# TOP_LED.net
KiCad netlist of a schematic drawn in Altium Designer
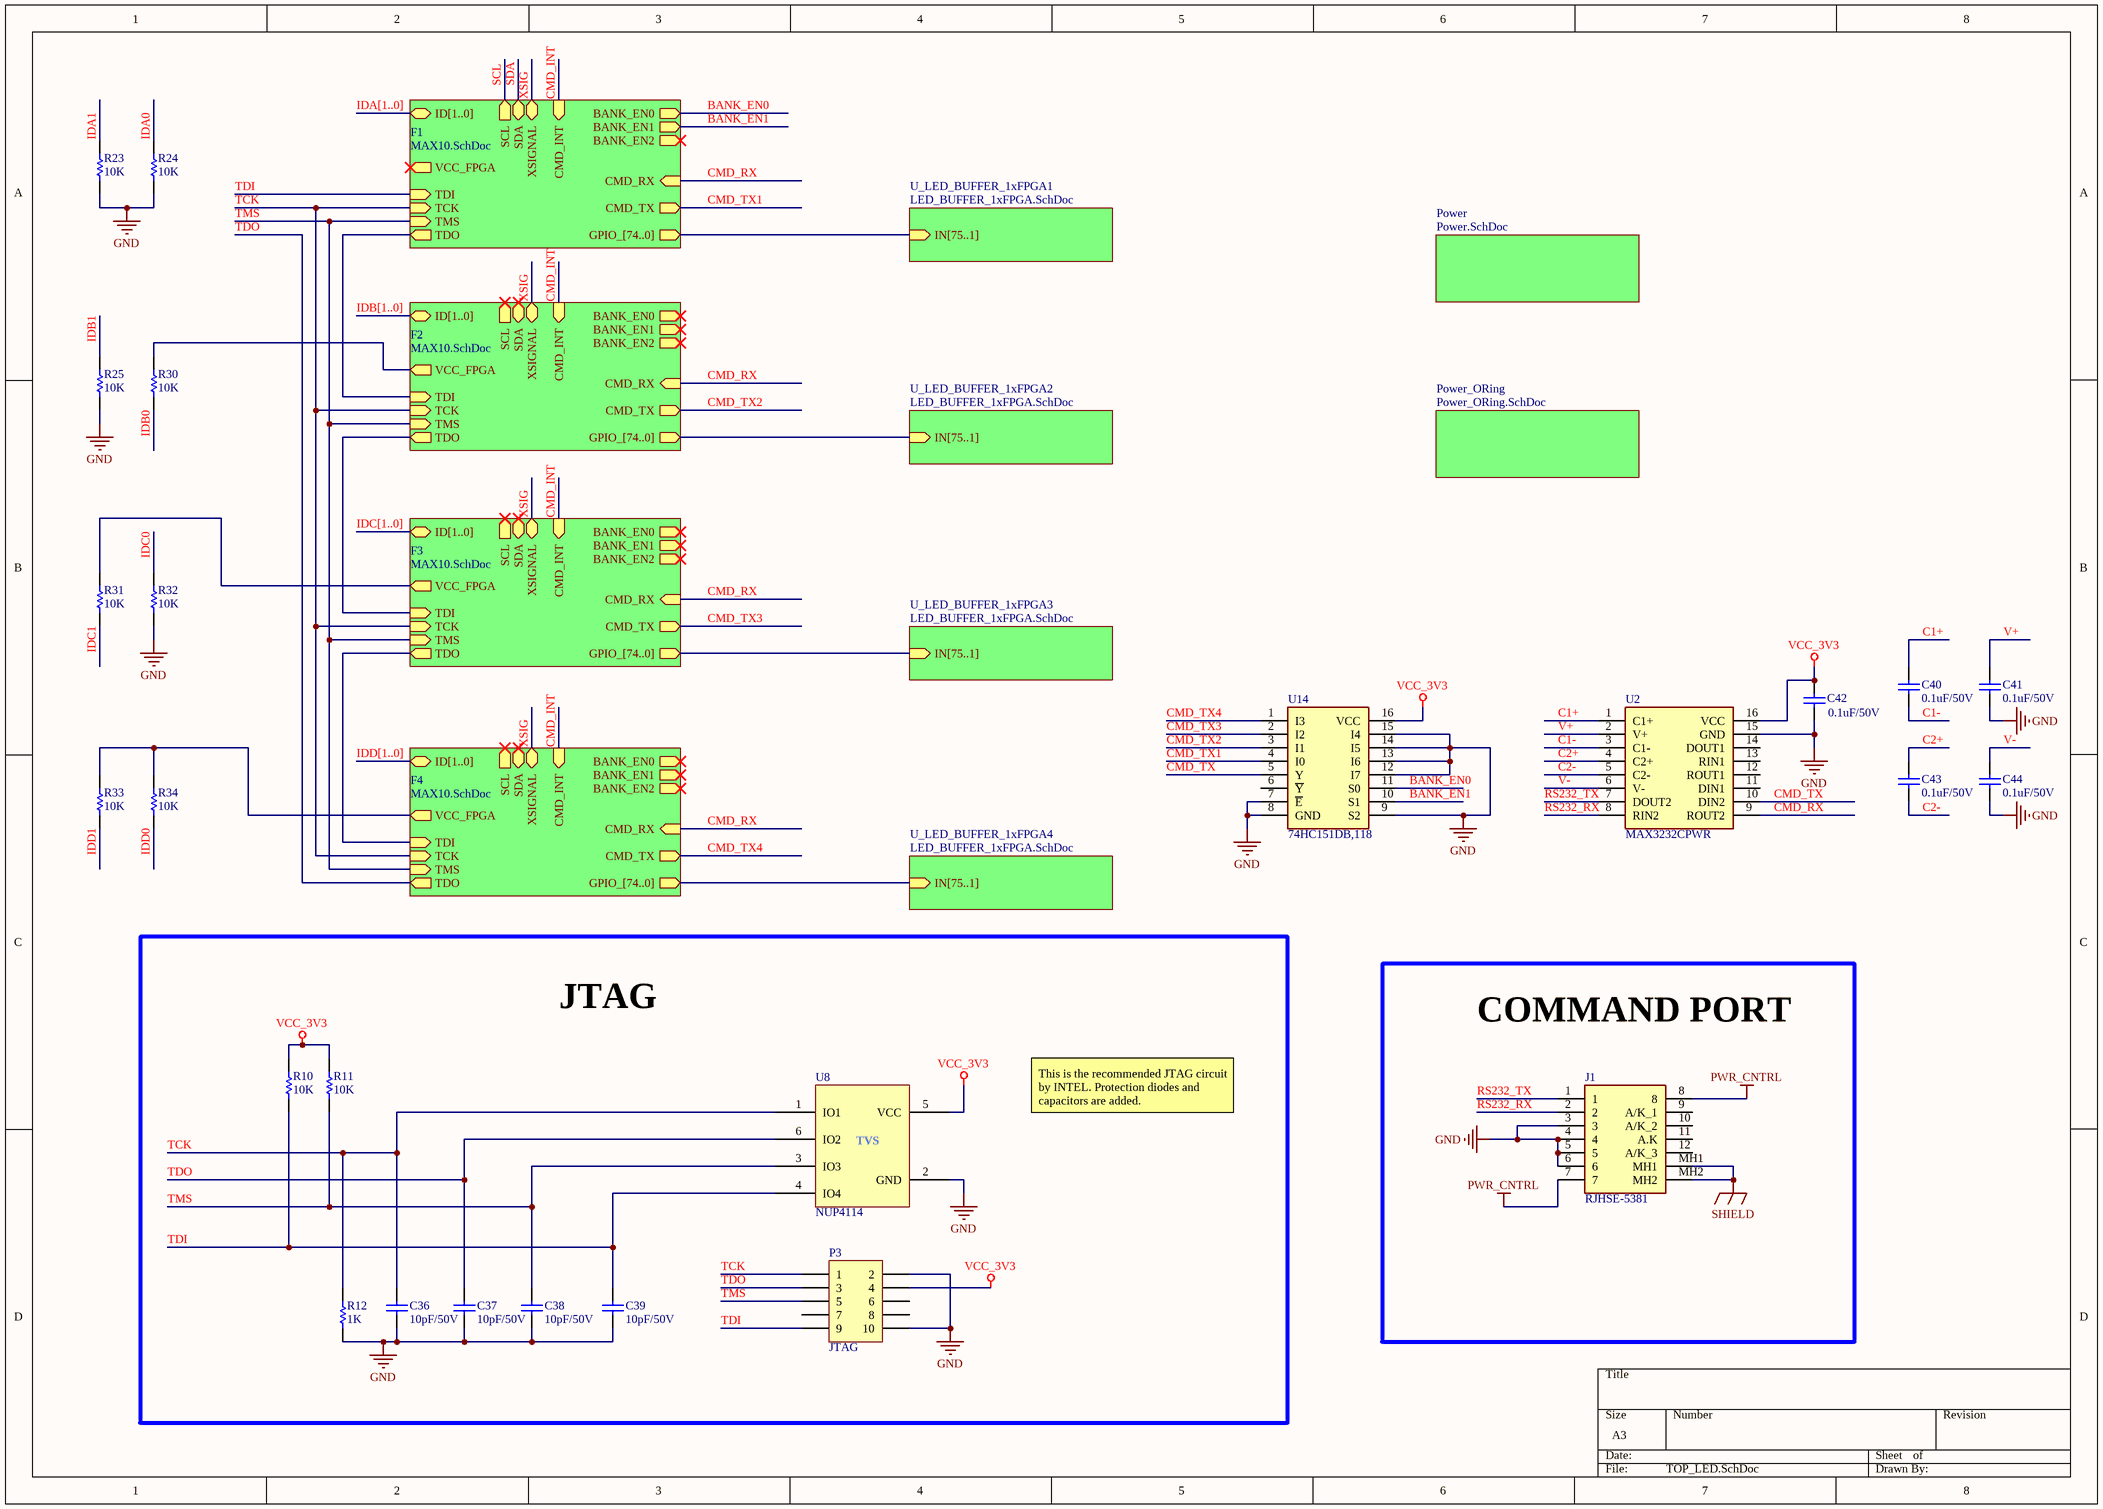
[diagram p0: TOP_LED.SchDoc]

(export (version "E")
  (design (tool "Eeschema 10.0.6"))
  (components
    (comp (ref "C36")
      (value "10pF/50V")
      (footprint "0603C")
      (description "Multilayer Ceramic Capacitors MLCC - SMD/SMT 50V 10pF 0603 C0G 5% AEC-Q200")
      (fields (field (name "MFR") "KEMET") (field (name "MFR PART NO") "C0603C100J5GACAUTO"))
      (libsource (lib "Miscellaneous Devices") (part "Cap"))
    )
    (comp (ref "C37")
      (value "10pF/50V")
      (footprint "0603C")
      (description "Multilayer Ceramic Capacitors MLCC - SMD/SMT 50V 10pF 0603 C0G 5% AEC-Q200")
      (fields (field (name "MFR") "KEMET") (field (name "MFR PART NO") "C0603C100J5GACAUTO"))
      (libsource (lib "Miscellaneous Devices") (part "Cap"))
    )
    (comp (ref "C38")
      (value "10pF/50V")
      (footprint "0603C")
      (description "Multilayer Ceramic Capacitors MLCC - SMD/SMT 50V 10pF 0603 C0G 5% AEC-Q200")
      (fields (field (name "MFR") "KEMET") (field (name "MFR PART NO") "C0603C100J5GACAUTO"))
      (libsource (lib "Miscellaneous Devices") (part "Cap"))
    )
    (comp (ref "C39")
      (value "10pF/50V")
      (footprint "0603C")
      (description "Multilayer Ceramic Capacitors MLCC - SMD/SMT 50V 10pF 0603 C0G 5% AEC-Q200")
      (fields (field (name "MFR") "KEMET") (field (name "MFR PART NO") "C0603C100J5GACAUTO"))
      (libsource (lib "Miscellaneous Devices") (part "Cap"))
    )
    (comp (ref "C40")
      (value "0.1uF/50V")
      (footprint "0603C")
      (description "Multilayer Ceramic Capacitors MLCC - SMD/SMT 50V 0.1uF 0603 X7R 20%")
      (fields (field (name "MFR") "KEMET") (field (name "MFR PART NO") "C0603C104M5RACTU"))
      (libsource (lib "Miscellaneous Devices") (part "Cap"))
    )
    (comp (ref "C41")
      (value "0.1uF/50V")
      (footprint "0603C")
      (description "Multilayer Ceramic Capacitors MLCC - SMD/SMT 50V 0.1uF 0603 X7R 20%")
      (fields (field (name "MFR") "KEMET") (field (name "MFR PART NO") "C0603C104M5RACTU"))
      (libsource (lib "Miscellaneous Devices") (part "Cap"))
    )
    (comp (ref "C42")
      (value "0.1uF/50V")
      (footprint "0603C")
      (description "Multilayer Ceramic Capacitors MLCC - SMD/SMT 50V 0.1uF 0603 X7R 20%")
      (fields (field (name "MFR") "KEMET") (field (name "MFR PART NO") "C0603C104M5RACTU"))
      (libsource (lib "Miscellaneous Devices") (part "Cap"))
    )
    (comp (ref "C43")
      (value "0.1uF/50V")
      (footprint "0603C")
      (description "Multilayer Ceramic Capacitors MLCC - SMD/SMT 50V 0.1uF 0603 X7R 20%")
      (fields (field (name "MFR") "KEMET") (field (name "MFR PART NO") "C0603C104M5RACTU"))
      (libsource (lib "Miscellaneous Devices") (part "Cap"))
    )
    (comp (ref "C44")
      (value "0.1uF/50V")
      (footprint "0603C")
      (description "Multilayer Ceramic Capacitors MLCC - SMD/SMT 50V 0.1uF 0603 X7R 20%")
      (fields (field (name "MFR") "KEMET") (field (name "MFR PART NO") "C0603C104M5RACTU"))
      (libsource (lib "Miscellaneous Devices") (part "Cap"))
    )
    (comp (ref "J1")
      (value "RJHSE-5381")
      (footprint "ProjCLib:RJHSE5381")
      (description "Modular Connectors / Ethernet Connectors R/A RJ45 SHEILDED 8 CONT Y/G LEDS")
      (fields
        (field (name "MFR") "Amphenol Commercial Products")
        (field (name "STOCKIEST PART NO") "523-RJHSE-5381")
      )
      (libsource (lib "*") (part "RJHSE-5381"))
    )
    (comp (ref "P3")
      (value "JTAG")
      (footprint "HDR2X5")
      (description "Header, 5-Pin, Dual row")
      (libsource (lib "Miscellaneous Connectors") (part "Header 5X2"))
    )
    (comp (ref "R10")
      (value "10K")
      (footprint "0603R")
      (description "Thick Film Resistors - SMD 0603 10Kohms 1% Anti-Sulfur AEC-Q200")
      (fields (field (name "MFR") "ROHM Semiconductor") (field (name "MFR PART NO") "SFR03EZPF1002"))
      (libsource (lib "Miscellaneous Devices") (part "Res1"))
    )
    (comp (ref "R11")
      (value "10K")
      (footprint "0603R")
      (description "Thick Film Resistors - SMD 0603 10Kohms 1% Anti-Sulfur AEC-Q200")
      (fields (field (name "MFR") "ROHM Semiconductor") (field (name "MFR PART NO") "SFR03EZPF1002"))
      (libsource (lib "Miscellaneous Devices") (part "Res1"))
    )
    (comp (ref "R12")
      (value "1K")
      (footprint "0603R")
      (description "Resistor")
      (fields (field (name "MFR") "Vishay / Dale") (field (name "MFR PART NO") "CRCW06031K00FKEAC"))
      (libsource (lib "Miscellaneous Devices") (part "Res1"))
    )
    (comp (ref "R23")
      (value "10K")
      (footprint "0603R")
      (description "Thick Film Resistors - SMD 0603 10Kohms 1% Anti-Sulfur AEC-Q200")
      (fields (field (name "MFR") "ROHM Semiconductor") (field (name "MFR PART NO") "SFR03EZPF1002"))
      (libsource (lib "Miscellaneous Devices") (part "Res1"))
    )
    (comp (ref "R24")
      (value "10K")
      (footprint "0603R")
      (description "Thick Film Resistors - SMD 0603 10Kohms 1% Anti-Sulfur AEC-Q200")
      (fields (field (name "MFR") "ROHM Semiconductor") (field (name "MFR PART NO") "SFR03EZPF1002"))
      (libsource (lib "Miscellaneous Devices") (part "Res1"))
    )
    (comp (ref "R25")
      (value "10K")
      (footprint "0603R")
      (description "Thick Film Resistors - SMD 0603 10Kohms 1% Anti-Sulfur AEC-Q200")
      (fields (field (name "MFR") "ROHM Semiconductor") (field (name "MFR PART NO") "SFR03EZPF1002"))
      (libsource (lib "Miscellaneous Devices") (part "Res1"))
    )
    (comp (ref "R30")
      (value "10K")
      (footprint "0603R")
      (description "Thick Film Resistors - SMD 0603 10Kohms 1% Anti-Sulfur AEC-Q200")
      (fields (field (name "MFR") "ROHM Semiconductor") (field (name "MFR PART NO") "SFR03EZPF1002"))
      (libsource (lib "Miscellaneous Devices") (part "Res1"))
    )
    (comp (ref "R31")
      (value "10K")
      (footprint "0603R")
      (description "Thick Film Resistors - SMD 0603 10Kohms 1% Anti-Sulfur AEC-Q200")
      (fields (field (name "MFR") "ROHM Semiconductor") (field (name "MFR PART NO") "SFR03EZPF1002"))
      (libsource (lib "Miscellaneous Devices") (part "Res1"))
    )
    (comp (ref "R32")
      (value "10K")
      (footprint "0603R")
      (description "Thick Film Resistors - SMD 0603 10Kohms 1% Anti-Sulfur AEC-Q200")
      (fields (field (name "MFR") "ROHM Semiconductor") (field (name "MFR PART NO") "SFR03EZPF1002"))
      (libsource (lib "Miscellaneous Devices") (part "Res1"))
    )
    (comp (ref "R33")
      (value "10K")
      (footprint "0603R")
      (description "Thick Film Resistors - SMD 0603 10Kohms 1% Anti-Sulfur AEC-Q200")
      (fields (field (name "MFR") "ROHM Semiconductor") (field (name "MFR PART NO") "SFR03EZPF1002"))
      (libsource (lib "Miscellaneous Devices") (part "Res1"))
    )
    (comp (ref "R34")
      (value "10K")
      (footprint "0603R")
      (description "Thick Film Resistors - SMD 0603 10Kohms 1% Anti-Sulfur AEC-Q200")
      (fields (field (name "MFR") "ROHM Semiconductor") (field (name "MFR PART NO") "SFR03EZPF1002"))
      (libsource (lib "Miscellaneous Devices") (part "Res1"))
    )
    (comp (ref "U2")
      (value "MAX3232CPWR")
      (footprint "MAX3232CPWR")
      (description "RS-232 Interface IC 3-5.5V Mult-Ch RS232")
      (fields (field (name "MFR") "Texas Instruments") (field (name "STOCKIEST PART NO") "595-MAX3232CPWR"))
      (libsource (lib "*") (part "MAX3232CPWR"))
    )
    (comp (ref "U8")
      (value "NUP4114")
      (footprint "NUP4114HMR6T1G")
      (description "ESD Suppressors / TVS Diodes LOW CAP TVS ARRAY 5.5V")
      (fields (field (name "MFR") "ON SEMI") (field (name "MFR PART NO") "NUP4114HMR6T1G"))
      (libsource (lib "Schlib1") (part "NUP4114"))
    )
    (comp (ref "U14")
      (value "74HC151DB,118")
      (footprint "74HC151DB,118")
      (description "Encoders, Decoders, Multiplexers & Demultiplexers 8-INPUT MULTIPLEXER")
      (fields (field (name "MFR") "NEXPERIA") (field (name "STOCKIEST PART NO") "771-HC151DB118"))
      (libsource (lib "*") (part "74HC151DB,118"))
    )
  )
  (nets
    (net (code "1") (name "/BANK_EN0") (class "Default")
      (node (ref "U14") (pin "11") (pinfunction "S0_11") (pintype "passive"))
    )
    (net (code "5") (name "/BANK_EN1") (class "Default")
      (node (ref "U14") (pin "10") (pinfunction "S1_10") (pintype "passive"))
    )
    (net (code "13") (name "/C1+") (class "Default")
      (node (ref "C40") (pin "2") (pinfunction "2_2") (pintype "passive"))
      (node (ref "U2") (pin "1") (pinfunction "C1+_1") (pintype "passive"))
    )
    (net (code "14") (name "/C1-") (class "Default")
      (node (ref "C40") (pin "1") (pinfunction "1_1") (pintype "passive"))
      (node (ref "U2") (pin "3") (pinfunction "C1-_3") (pintype "passive"))
    )
    (net (code "15") (name "/C2+") (class "Default")
      (node (ref "C43") (pin "2") (pinfunction "2_2") (pintype "passive"))
      (node (ref "U2") (pin "4") (pinfunction "C2+_4") (pintype "passive"))
    )
    (net (code "16") (name "/C2-") (class "Default")
      (node (ref "C43") (pin "1") (pinfunction "1_1") (pintype "passive"))
      (node (ref "U2") (pin "5") (pinfunction "C2-_5") (pintype "passive"))
    )
    (net (code "18") (name "/CMD_RX") (class "Default")
      (node (ref "U2") (pin "9") (pinfunction "ROUT2_9") (pintype "passive"))
    )
    (net (code "19") (name "/CMD_TX") (class "Default")
      (node (ref "U14") (pin "5") (pinfunction "Y_5") (pintype "passive"))
      (node (ref "U2") (pin "10") (pinfunction "DIN2_10") (pintype "passive"))
    )
    (net (code "20") (name "/CMD_TX1") (class "Default")
      (node (ref "U14") (pin "4") (pinfunction "I0_4") (pintype "passive"))
    )
    (net (code "21") (name "/CMD_TX2") (class "Default")
      (node (ref "U14") (pin "3") (pinfunction "I1_3") (pintype "passive"))
    )
    (net (code "22") (name "/CMD_TX3") (class "Default")
      (node (ref "U14") (pin "2") (pinfunction "I2_2") (pintype "passive"))
    )
    (net (code "23") (name "/CMD_TX4") (class "Default")
      (node (ref "U14") (pin "1") (pinfunction "I3_1") (pintype "passive"))
    )
    (net (code "28") (name "/IDA0") (class "Default")
      (node (ref "R24") (pin "1") (pinfunction "1_1") (pintype "passive"))
    )
    (net (code "29") (name "/IDA1") (class "Default")
      (node (ref "R23") (pin "1") (pinfunction "1_1") (pintype "passive"))
    )
    (net (code "31") (name "/IDB0") (class "Default")
      (node (ref "R30") (pin "2") (pinfunction "2_2") (pintype "passive"))
    )
    (net (code "32") (name "/IDB1") (class "Default")
      (node (ref "R25") (pin "1") (pinfunction "1_1") (pintype "passive"))
    )
    (net (code "34") (name "/IDC0") (class "Default")
      (node (ref "R32") (pin "1") (pinfunction "1_1") (pintype "passive"))
    )
    (net (code "35") (name "/IDC1") (class "Default")
      (node (ref "R31") (pin "2") (pinfunction "2_2") (pintype "passive"))
    )
    (net (code "37") (name "/IDD0") (class "Default")
      (node (ref "R34") (pin "2") (pinfunction "2_2") (pintype "passive"))
    )
    (net (code "38") (name "/IDD1") (class "Default")
      (node (ref "R33") (pin "2") (pinfunction "2_2") (pintype "passive"))
    )
    (net (code "40") (name "/RS232_RX") (class "Default")
      (node (ref "J1") (pin "2") (pinfunction "2_2") (pintype "passive"))
      (node (ref "U2") (pin "8") (pinfunction "RIN2_8") (pintype "passive"))
    )
    (net (code "41") (name "/RS232_TX") (class "Default")
      (node (ref "J1") (pin "1") (pinfunction "1_1") (pintype "passive"))
      (node (ref "U2") (pin "7") (pinfunction "DOUT2_7") (pintype "passive"))
    )
    (net (code "50") (name "/TCK") (class "Default")
      (node (ref "C36") (pin "2") (pinfunction "2_2") (pintype "passive"))
      (node (ref "P3") (pin "1") (pinfunction "1_1") (pintype "passive"))
      (node (ref "R12") (pin "2") (pinfunction "2_2") (pintype "passive"))
      (node (ref "U8") (pin "1") (pinfunction "IO1_1") (pintype "passive"))
    )
    (net (code "51") (name "/TDI") (class "Default")
      (node (ref "C39") (pin "2") (pinfunction "2_2") (pintype "passive"))
      (node (ref "P3") (pin "9") (pinfunction "9_9") (pintype "passive"))
      (node (ref "R10") (pin "2") (pinfunction "2_2") (pintype "passive"))
      (node (ref "U8") (pin "4") (pinfunction "IO4_4") (pintype "passive"))
    )
    (net (code "52") (name "/TDO") (class "Default")
      (node (ref "C37") (pin "2") (pinfunction "2_2") (pintype "passive"))
      (node (ref "P3") (pin "3") (pinfunction "3_3") (pintype "passive"))
      (node (ref "U8") (pin "6") (pinfunction "IO2_6") (pintype "passive"))
    )
    (net (code "56") (name "/TMS") (class "Default")
      (node (ref "C38") (pin "2") (pinfunction "2_2") (pintype "passive"))
      (node (ref "P3") (pin "5") (pinfunction "5_5") (pintype "passive"))
      (node (ref "R11") (pin "2") (pinfunction "2_2") (pintype "passive"))
      (node (ref "U8") (pin "3") (pinfunction "IO3_3") (pintype "passive"))
    )
    (net (code "57") (name "/V+") (class "Default")
      (node (ref "C41") (pin "2") (pinfunction "2_2") (pintype "passive"))
      (node (ref "U2") (pin "2") (pinfunction "V+_2") (pintype "passive"))
    )
    (net (code "58") (name "/V-") (class "Default")
      (node (ref "C44") (pin "2") (pinfunction "2_2") (pintype "passive"))
      (node (ref "U2") (pin "6") (pinfunction "V-_6") (pintype "passive"))
    )
    (net (code "59") (name "/VCC_FPGA") (class "Default")
      (node (ref "R30") (pin "1") (pinfunction "1_1") (pintype "passive"))
    )
    (net (code "60") (name "/VCC_FPGA_1") (class "Default")
      (node (ref "R33") (pin "1") (pinfunction "1_1") (pintype "passive"))
      (node (ref "R34") (pin "1") (pinfunction "1_1") (pintype "passive"))
    )
    (net (code "61") (name "/VCC_FPGA_2") (class "Default")
      (node (ref "R31") (pin "1") (pinfunction "1_1") (pintype "passive"))
    )
    (net (code "64") (name "GND") (class "Default")
      (node (ref "C36") (pin "1") (pinfunction "1_1") (pintype "passive"))
      (node (ref "C37") (pin "1") (pinfunction "1_1") (pintype "passive"))
      (node (ref "C38") (pin "1") (pinfunction "1_1") (pintype "passive"))
      (node (ref "C39") (pin "1") (pinfunction "1_1") (pintype "passive"))
      (node (ref "C41") (pin "1") (pinfunction "1_1") (pintype "passive"))
      (node (ref "C42") (pin "1") (pinfunction "1_1") (pintype "passive"))
      (node (ref "C44") (pin "1") (pinfunction "1_1") (pintype "passive"))
      (node (ref "J1") (pin "3") (pinfunction "3_3") (pintype "passive"))
      (node (ref "J1") (pin "4") (pinfunction "4_4") (pintype "passive"))
      (node (ref "J1") (pin "5") (pinfunction "5_5") (pintype "passive"))
      (node (ref "J1") (pin "6") (pinfunction "6_6") (pintype "passive"))
      (node (ref "P3") (pin "10") (pinfunction "10_10") (pintype "passive"))
      (node (ref "P3") (pin "2") (pinfunction "2_2") (pintype "passive"))
      (node (ref "R12") (pin "1") (pinfunction "1_1") (pintype "passive"))
      (node (ref "R23") (pin "2") (pinfunction "2_2") (pintype "passive"))
      (node (ref "R24") (pin "2") (pinfunction "2_2") (pintype "passive"))
      (node (ref "R25") (pin "2") (pinfunction "2_2") (pintype "passive"))
      (node (ref "R32") (pin "2") (pinfunction "2_2") (pintype "passive"))
      (node (ref "U14") (pin "12") (pinfunction "I7_12") (pintype "passive"))
      (node (ref "U14") (pin "13") (pinfunction "I6_13") (pintype "passive"))
      (node (ref "U14") (pin "14") (pinfunction "I5_14") (pintype "passive"))
      (node (ref "U14") (pin "15") (pinfunction "I4_15") (pintype "passive"))
      (node (ref "U14") (pin "7") (pinfunction "~{E}_7") (pintype "passive"))
      (node (ref "U14") (pin "8") (pinfunction "GND_8") (pintype "passive"))
      (node (ref "U14") (pin "9") (pinfunction "S2_9") (pintype "passive"))
      (node (ref "U2") (pin "15") (pinfunction "GND_15") (pintype "passive"))
      (node (ref "U8") (pin "2") (pinfunction "GND_2") (pintype "passive"))
    )
    (net (code "65") (name "PWR_CNTRL") (class "Default")
      (node (ref "J1") (pin "7") (pinfunction "7_7") (pintype "passive"))
      (node (ref "J1") (pin "8") (pinfunction "8_8") (pintype "passive"))
    )
    (net (code "66") (name "SHIELD") (class "Default")
      (node (ref "J1") (pin "MH1") (pinfunction "MH1_MH1") (pintype "passive"))
      (node (ref "J1") (pin "MH2") (pinfunction "MH2_MH2") (pintype "passive"))
    )
    (net (code "67") (name "VCC_3V3") (class "Default")
      (node (ref "C42") (pin "2") (pinfunction "2_2") (pintype "passive"))
      (node (ref "P3") (pin "4") (pinfunction "4_4") (pintype "passive"))
      (node (ref "R10") (pin "1") (pinfunction "1_1") (pintype "passive"))
      (node (ref "R11") (pin "1") (pinfunction "1_1") (pintype "passive"))
      (node (ref "U14") (pin "16") (pinfunction "VCC_16") (pintype "passive"))
      (node (ref "U2") (pin "16") (pinfunction "VCC_16") (pintype "passive"))
      (node (ref "U8") (pin "5") (pinfunction "VCC_5") (pintype "passive"))
    )
    (net (code "68") (name "unconnected-(J1-A.K-Pad11)") (class "Default")
      (node (ref "J1") (pin "11") (pinfunction "A.K_11") (pintype "passive"))
    )
    (net (code "69") (name "unconnected-(J1-A{slash}K_1-Pad9)") (class "Default")
      (node (ref "J1") (pin "9") (pinfunction "A/K_1_9") (pintype "passive"))
    )
    (net (code "70") (name "unconnected-(J1-A{slash}K_2-Pad10)") (class "Default")
      (node (ref "J1") (pin "10") (pinfunction "A/K_2_10") (pintype "passive"))
    )
    (net (code "71") (name "unconnected-(J1-A{slash}K_3-Pad12)") (class "Default")
      (node (ref "J1") (pin "12") (pinfunction "A/K_3_12") (pintype "passive"))
    )
    (net (code "72") (name "unconnected-(P3-Pad6)") (class "Default")
      (node (ref "P3") (pin "6") (pinfunction "6_6") (pintype "passive"))
    )
    (net (code "73") (name "unconnected-(P3-Pad7)") (class "Default")
      (node (ref "P3") (pin "7") (pinfunction "7_7") (pintype "passive"))
    )
    (net (code "74") (name "unconnected-(P3-Pad8)") (class "Default")
      (node (ref "P3") (pin "8") (pinfunction "8_8") (pintype "passive"))
    )
    (net (code "75") (name "unconnected-(U2-DIN1-Pad11)") (class "Default")
      (node (ref "U2") (pin "11") (pinfunction "DIN1_11") (pintype "passive"))
    )
    (net (code "76") (name "unconnected-(U2-DOUT1-Pad14)") (class "Default")
      (node (ref "U2") (pin "14") (pinfunction "DOUT1_14") (pintype "passive"))
    )
    (net (code "77") (name "unconnected-(U2-RIN1-Pad13)") (class "Default")
      (node (ref "U2") (pin "13") (pinfunction "RIN1_13") (pintype "passive"))
    )
    (net (code "78") (name "unconnected-(U2-ROUT1-Pad12)") (class "Default")
      (node (ref "U2") (pin "12") (pinfunction "ROUT1_12") (pintype "passive"))
    )
    (net (code "79") (name "unconnected-(U14-~{Y}-Pad6)") (class "Default")
      (node (ref "U14") (pin "6") (pinfunction "~{Y}_6") (pintype "passive"))
    )
  )
)
